# Automatic_Water_Level_Controller_-_prof_.net
KiCad netlist of a schematic drawn in Altium Designer
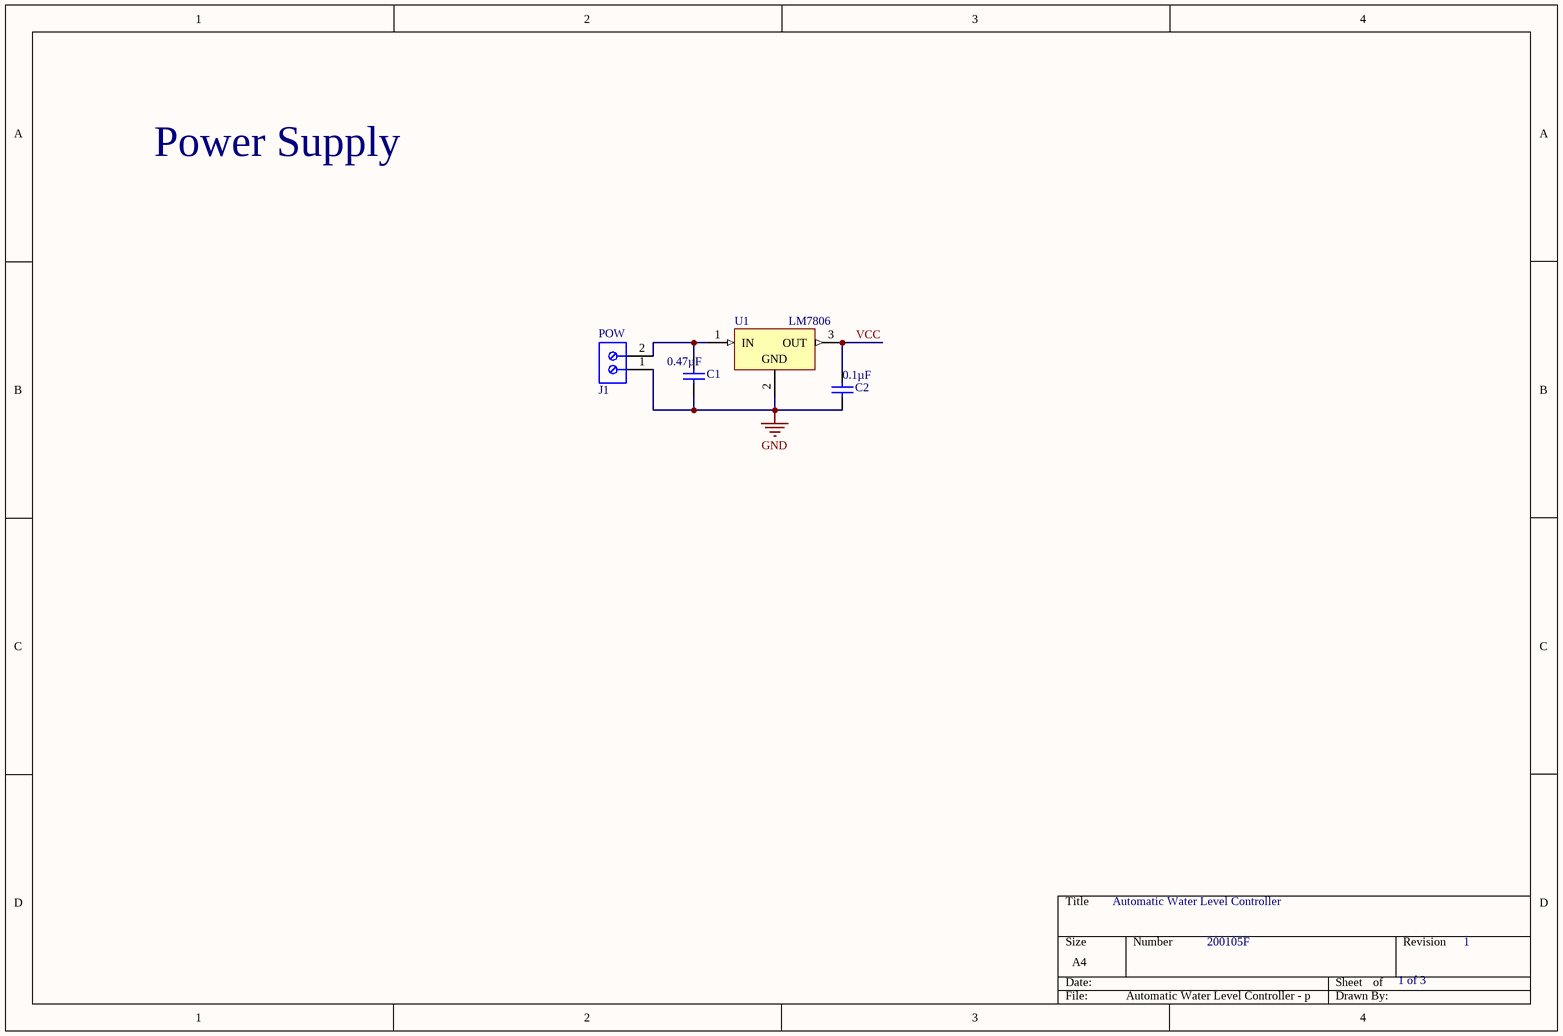
[diagram p0: Automatic Water Level Controller - prof.jayasinghe.SchDoc]

(export (version "E")
  (design (tool "Eeschema 10.0.6"))
  (components
    (comp (ref "C1")
      (value "C330C105M5U5TA")
      (footprint "KEMT-C330C105M5U5TA")
      (description "Ceramic Capacitor, 1 uF, +/- 20%, 50 V, -10 to 85 degC, 2-Pin THD, RoHS, Bulk")
      (fields
        (field (name "TOLERANCE") "±20%")
        (field (name "CAPACITANCE") "0.47µF")
        (field (name "MANUFACTURER") "Kemet")
      )
      (libsource (lib "Altium Content Vault") (part "CAP-NP-2"))
    )
    (comp (ref "C2")
      (value "C330C105M5U5TA")
      (footprint "KEMT-C330C105M5U5TA")
      (description "Ceramic Capacitor, 1 uF, +/- 20%, 50 V, -10 to 85 degC, 2-Pin THD, RoHS, Bulk")
      (fields
        (field (name "TOLERANCE") "±20%")
        (field (name "CAPACITANCE") "0.1µF")
        (field (name "MANUFACTURER") "Kemet")
      )
      (libsource (lib "Altium Content Vault") (part "CAP-NP-2"))
    )
    (comp (ref "J1")
      (value "POW")
      (footprint "691102710002")
      (description "Series 102 - 5.00 mm Horizontal Entry Modular with Pressure Clamp WR-TBL, 2 pin")
      (fields
        (field (name "MANUFACTURER") "Wurth Elektronik")
        (field (name "PART NUMBER") "691102710002")
        (field (name "PUBLISHER") "WurthElektronik")
      )
      (libsource (lib "Altium Content Vault") (part "WE-CN-1P-F-TB2"))
    )
    (comp (ref "U1")
      (value "LM7806")
      (footprint "FAIR-TO-220-3")
      (description "Positive Voltage Regulator, 5 V, 1 A, -40 to 125 degC, 3-Pin TO-220, RoHS, Tube")
      (fields (field (name "MANUFACTURER") "FairchildSemiconductor"))
      (libsource (lib "Altium Content Vault") (part "FAIR-LM7805CT-TO220-3"))
    )
  )
  (nets
    (net (code "1") (name "/VCC") (class "Default")
      (node (ref "C2") (pin "2") (pinfunction "2_2") (pintype "passive"))
      (node (ref "U1") (pin "3") (pinfunction "OUT_3") (pintype "output"))
    )
    (net (code "2") (name "GND") (class "Default")
      (node (ref "C1") (pin "1") (pinfunction "1_1") (pintype "passive"))
      (node (ref "C2") (pin "1") (pinfunction "1_1") (pintype "passive"))
      (node (ref "J1") (pin "1") (pinfunction "1_1") (pintype "passive"))
      (node (ref "U1") (pin "2") (pinfunction "GND_2") (pintype "power_in"))
    )
    (net (code "3") (name "Net-(U1-IN)") (class "Default")
      (node (ref "C1") (pin "2") (pinfunction "2_2") (pintype "passive"))
      (node (ref "J1") (pin "2") (pinfunction "2_2") (pintype "passive"))
      (node (ref "U1") (pin "1") (pinfunction "IN_1") (pintype "input"))
    )
  )
)
